# magnet-node.net
KiCad netlist of a schematic drawn in EAGLE
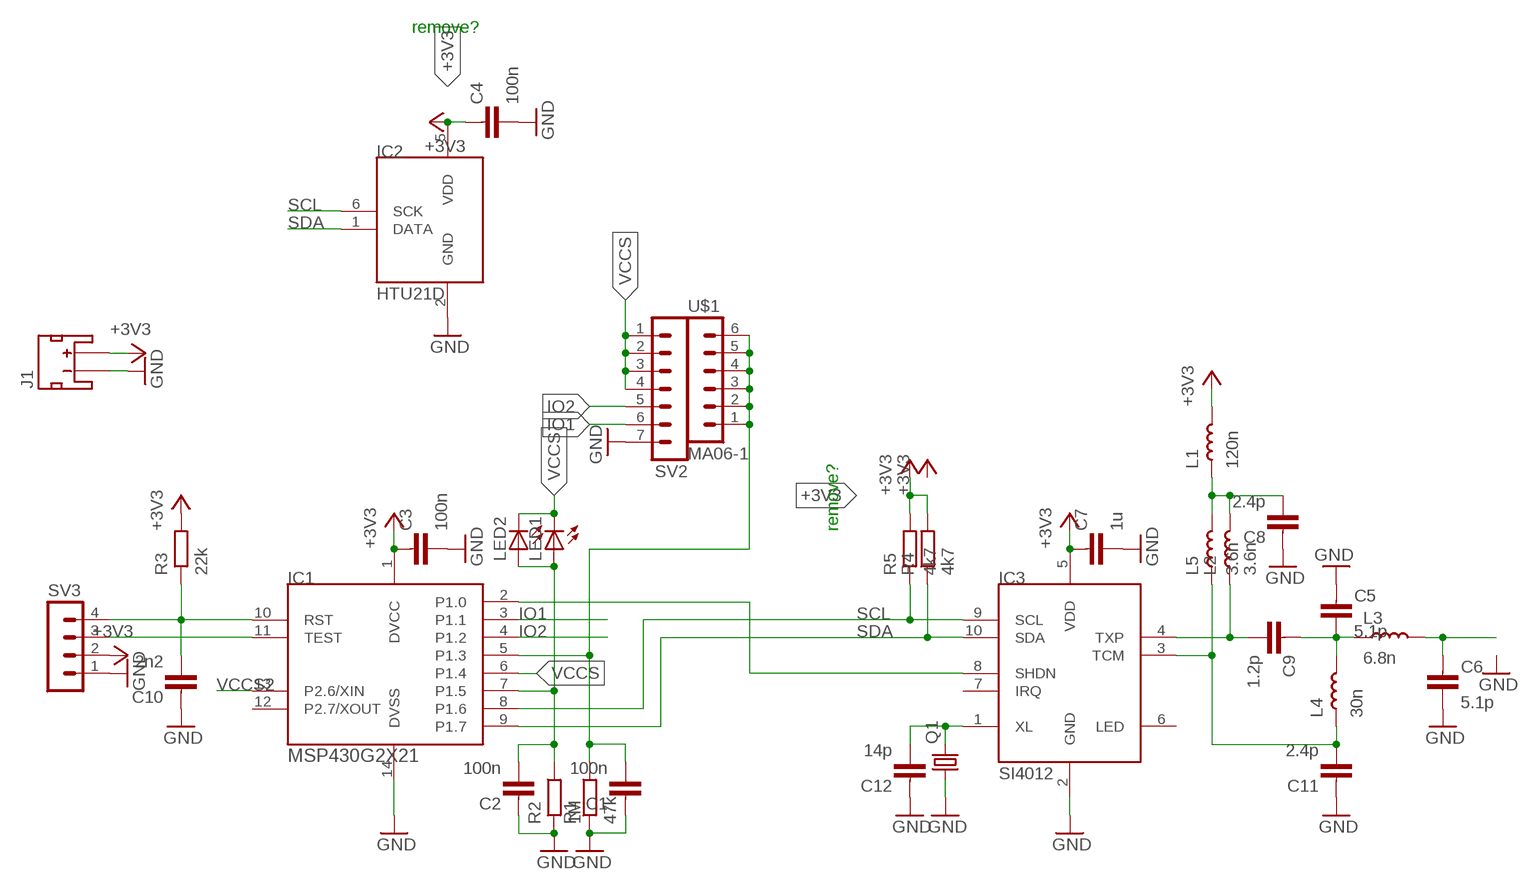
[diagram p0: schematic, sheet 1]

(export (version "E")
  (design (tool "Eeschema 10.0.6"))
  (components
    (comp (ref "C1")
      (value "100n")
      (footprint "eagle-import:C0603-N")
      (libsource (lib "eagle-import") (part "CAPACITOR0603-N"))
    )
    (comp (ref "C2")
      (value "100n")
      (footprint "eagle-import:C0603-N")
      (libsource (lib "eagle-import") (part "CAPACITOR0603-N"))
    )
    (comp (ref "C3")
      (value "100n")
      (footprint "eagle-import:C0603-N")
      (libsource (lib "eagle-import") (part "CAPACITOR0603-N"))
    )
    (comp (ref "C4")
      (value "100n")
      (footprint "eagle-import:C0603-N")
      (libsource (lib "eagle-import") (part "CAPACITOR0603-N"))
    )
    (comp (ref "C5")
      (value "5.1p")
      (footprint "eagle-import:C0603-N")
      (libsource (lib "eagle-import") (part "CAPACITOR0603-N"))
    )
    (comp (ref "C6")
      (value "5.1p")
      (footprint "eagle-import:C0603-N")
      (libsource (lib "eagle-import") (part "CAPACITOR0603-N"))
    )
    (comp (ref "C7")
      (value "1u")
      (footprint "eagle-import:C0603-N")
      (libsource (lib "eagle-import") (part "CAPACITOR0603-N"))
    )
    (comp (ref "C8")
      (value "2.4p")
      (footprint "eagle-import:C0603-N")
      (libsource (lib "eagle-import") (part "CAPACITOR0603-N"))
    )
    (comp (ref "C9")
      (value "1.2p")
      (footprint "eagle-import:C0603-N")
      (libsource (lib "eagle-import") (part "CAPACITOR0603-N"))
    )
    (comp (ref "C10")
      (value "2n2")
      (footprint "eagle-import:C0603-N")
      (libsource (lib "eagle-import") (part "CAPACITOR0603-N"))
    )
    (comp (ref "C11")
      (value "2.4p")
      (footprint "eagle-import:C0603-N")
      (libsource (lib "eagle-import") (part "CAPACITOR0603-N"))
    )
    (comp (ref "C12")
      (value "14p")
      (footprint "eagle-import:C0603-N")
      (libsource (lib "eagle-import") (part "CAPACITOR0603-N"))
    )
    (comp (ref "IC1")
      (value "MSP430G2X21")
      (footprint "eagle-import:TSSOP14")
      (libsource (lib "eagle-import") (part "MSP430G2X21"))
    )
    (comp (ref "IC2")
      (value "HTU21D")
      (footprint "eagle-import:DFN6-L")
      (libsource (lib "eagle-import") (part "HTU21D"))
    )
    (comp (ref "IC3")
      (value "SI4012")
      (footprint "eagle-import:MSOP10")
      (libsource (lib "eagle-import") (part "SI4012"))
    )
    (comp (ref "J1")
      (value "JST_2MM_MALE_TH")
      (footprint "eagle-import:JST-2-TH")
      (libsource (lib "eagle-import") (part "JST_2MM_MALE_TH"))
    )
    (comp (ref "L1")
      (value "120n")
      (footprint "eagle-import:L0603-N")
      (libsource (lib "eagle-import") (part "INDUCTOR0603-N"))
    )
    (comp (ref "L2")
      (value "3.6n")
      (footprint "eagle-import:L0402-N")
      (libsource (lib "eagle-import") (part "INDUCTOR0402-N"))
    )
    (comp (ref "L3")
      (value "6.8n")
      (footprint "eagle-import:L0402-N")
      (libsource (lib "eagle-import") (part "INDUCTOR0402-N"))
    )
    (comp (ref "L4")
      (value "30n")
      (footprint "eagle-import:L0402-N")
      (libsource (lib "eagle-import") (part "INDUCTOR0402-N"))
    )
    (comp (ref "L5")
      (value "3.6n")
      (footprint "eagle-import:L0402-N")
      (libsource (lib "eagle-import") (part "INDUCTOR0402-N"))
    )
    (comp (ref "LED1")
      (value "LEDSMT1206")
      (footprint "eagle-import:1206")
      (libsource (lib "eagle-import") (part "LEDSMT1206"))
    )
    (comp (ref "LED2")
      (value "LEDSMT1206")
      (footprint "eagle-import:1206")
      (libsource (lib "eagle-import") (part "LEDSMT1206"))
    )
    (comp (ref "Q1")
      (value "CRYSTALHC49S")
      (footprint "eagle-import:HC49_S")
      (libsource (lib "eagle-import") (part "CRYSTALHC49S"))
    )
    (comp (ref "R1")
      (value "47k")
      (footprint "eagle-import:R0603-N")
      (libsource (lib "eagle-import") (part "RESISTOR0603-N"))
    )
    (comp (ref "R2")
      (value "1M")
      (footprint "eagle-import:R0603-N")
      (libsource (lib "eagle-import") (part "RESISTOR0603-N"))
    )
    (comp (ref "R3")
      (value "22k")
      (footprint "eagle-import:R0603-N")
      (libsource (lib "eagle-import") (part "RESISTOR0603-N"))
    )
    (comp (ref "R4")
      (value "4k7")
      (footprint "eagle-import:R0603-N")
      (libsource (lib "eagle-import") (part "RESISTOR0603-N"))
    )
    (comp (ref "R5")
      (value "4k7")
      (footprint "eagle-import:R0603-N")
      (libsource (lib "eagle-import") (part "RESISTOR0603-N"))
    )
    (comp (ref "SV2")
      (value "MA07-1S")
      (footprint "eagle-import:MA07-1-SMD")
      (libsource (lib "eagle-import") (part "MA07-1S"))
    )
    (comp (ref "SV3")
      (value "MA04-1E")
      (footprint "eagle-import:EDGE_4")
      (libsource (lib "eagle-import") (part "MA04-1E"))
    )
    (comp (ref "U$1")
      (value "MA06-1")
      (footprint "eagle-import:MA06-1-SMD")
      (libsource (lib "eagle-import") (part "MA06-1"))
    )
  )
  (nets
    (net (code "1") (name "+3V3") (class "Default")
      (node (ref "C3") (pin "1") (pinfunction "1_1") (pintype "passive"))
      (node (ref "C4") (pin "1") (pinfunction "1_1") (pintype "passive"))
      (node (ref "C7") (pin "1") (pinfunction "1_1") (pintype "passive"))
      (node (ref "IC1") (pin "1") (pinfunction "DVCC_1") (pintype "power_in"))
      (node (ref "IC2") (pin "5") (pinfunction "VDD_5") (pintype "power_in"))
      (node (ref "IC3") (pin "5") (pinfunction "VDD_5") (pintype "power_in"))
      (node (ref "J1") (pin "1") (pinfunction "+_1") (pintype "bidirectional"))
      (node (ref "L1") (pin "2") (pinfunction "P$2_2") (pintype "passive"))
      (node (ref "R3") (pin "2") (pinfunction "P$2_2") (pintype "passive"))
      (node (ref "R4") (pin "2") (pinfunction "P$2_2") (pintype "passive"))
      (node (ref "R5") (pin "2") (pinfunction "P$2_2") (pintype "passive"))
      (node (ref "SV3") (pin "2") (pinfunction "2_2") (pintype "passive"))
    )
    (net (code "2") (name "/SCL") (class "Default")
      (node (ref "IC1") (pin "8") (pinfunction "P1.6_8") (pintype "bidirectional"))
      (node (ref "IC2") (pin "6") (pinfunction "SCK_6") (pintype "input"))
      (node (ref "IC3") (pin "9") (pinfunction "SCL_9") (pintype "input"))
      (node (ref "R5") (pin "1") (pinfunction "P$1_1") (pintype "passive"))
    )
    (net (code "3") (name "/SDA") (class "Default")
      (node (ref "IC1") (pin "9") (pinfunction "P1.7_9") (pintype "bidirectional"))
      (node (ref "IC2") (pin "1") (pinfunction "DATA_1") (pintype "bidirectional"))
      (node (ref "IC3") (pin "10") (pinfunction "SDA_10") (pintype "bidirectional"))
      (node (ref "R4") (pin "1") (pinfunction "P$1_1") (pintype "passive"))
    )
    (net (code "4") (name "/VCCS2") (class "Default")
      (node (ref "IC1") (pin "13") (pinfunction "P2.6/XIN_13") (pintype "bidirectional"))
    )
    (net (code "5") (name "GND") (class "Default")
      (node (ref "C1") (pin "1") (pinfunction "1_1") (pintype "passive"))
      (node (ref "C10") (pin "1") (pinfunction "1_1") (pintype "passive"))
      (node (ref "C11") (pin "1") (pinfunction "1_1") (pintype "passive"))
      (node (ref "C12") (pin "1") (pinfunction "1_1") (pintype "passive"))
      (node (ref "C2") (pin "1") (pinfunction "1_1") (pintype "passive"))
      (node (ref "C3") (pin "2") (pinfunction "2_2") (pintype "passive"))
      (node (ref "C4") (pin "2") (pinfunction "2_2") (pintype "passive"))
      (node (ref "C5") (pin "1") (pinfunction "1_1") (pintype "passive"))
      (node (ref "C6") (pin "2") (pinfunction "2_2") (pintype "passive"))
      (node (ref "C7") (pin "2") (pinfunction "2_2") (pintype "passive"))
      (node (ref "C8") (pin "1") (pinfunction "1_1") (pintype "passive"))
      (node (ref "IC1") (pin "14") (pinfunction "DVSS_14") (pintype "power_in"))
      (node (ref "IC2") (pin "2") (pinfunction "GND_2") (pintype "power_in"))
      (node (ref "IC3") (pin "2") (pinfunction "GND_2") (pintype "power_in"))
      (node (ref "J1") (pin "2") (pinfunction "-_2") (pintype "bidirectional"))
      (node (ref "Q1") (pin "1") (pinfunction "1_1") (pintype "passive"))
      (node (ref "R1") (pin "1") (pinfunction "P$1_1") (pintype "passive"))
      (node (ref "R2") (pin "1") (pinfunction "P$1_1") (pintype "passive"))
      (node (ref "SV2") (pin "7") (pinfunction "7_7") (pintype "passive"))
      (node (ref "SV3") (pin "1") (pinfunction "1_1") (pintype "passive"))
    )
    (net (code "6") (name "IO1") (class "Default")
      (node (ref "IC1") (pin "3") (pinfunction "P1.1_3") (pintype "bidirectional"))
      (node (ref "SV2") (pin "6") (pinfunction "6_6") (pintype "passive"))
    )
    (net (code "7") (name "IO2") (class "Default")
      (node (ref "IC1") (pin "4") (pinfunction "P1.2_4") (pintype "bidirectional"))
      (node (ref "SV2") (pin "5") (pinfunction "5_5") (pintype "passive"))
    )
    (net (code "8") (name "Net-(IC1-P1.0)") (class "Default")
      (node (ref "IC1") (pin "2") (pinfunction "P1.0_2") (pintype "bidirectional"))
      (node (ref "IC3") (pin "8") (pinfunction "SHDN_8") (pintype "input"))
    )
    (net (code "9") (name "Net-(IC1-P1.3)") (class "Default")
      (node (ref "C1") (pin "2") (pinfunction "2_2") (pintype "passive"))
      (node (ref "IC1") (pin "5") (pinfunction "P1.3_5") (pintype "bidirectional"))
      (node (ref "R1") (pin "2") (pinfunction "P$2_2") (pintype "passive"))
      (node (ref "U$1") (pin "1") (pinfunction "1_1") (pintype "passive"))
      (node (ref "U$1") (pin "2") (pinfunction "2_2") (pintype "passive"))
      (node (ref "U$1") (pin "3") (pinfunction "3_3") (pintype "passive"))
      (node (ref "U$1") (pin "4") (pinfunction "4_4") (pintype "passive"))
      (node (ref "U$1") (pin "5") (pinfunction "5_5") (pintype "passive"))
      (node (ref "U$1") (pin "6") (pinfunction "6_6") (pintype "passive"))
    )
    (net (code "10") (name "Net-(IC1-P1.5)") (class "Default")
      (node (ref "C2") (pin "2") (pinfunction "2_2") (pintype "passive"))
      (node (ref "IC1") (pin "7") (pinfunction "P1.5_7") (pintype "bidirectional"))
      (node (ref "LED1") (pin "A") (pinfunction "A_A") (pintype "passive"))
      (node (ref "LED2") (pin "A") (pinfunction "A_A") (pintype "passive"))
      (node (ref "R2") (pin "2") (pinfunction "P$2_2") (pintype "passive"))
    )
    (net (code "11") (name "Net-(IC1-RST)") (class "Default")
      (node (ref "C10") (pin "2") (pinfunction "2_2") (pintype "passive"))
      (node (ref "IC1") (pin "10") (pinfunction "RST_10") (pintype "bidirectional"))
      (node (ref "R3") (pin "1") (pinfunction "P$1_1") (pintype "passive"))
      (node (ref "SV3") (pin "4") (pinfunction "4_4") (pintype "passive"))
    )
    (net (code "12") (name "Net-(IC1-TEST)") (class "Default")
      (node (ref "IC1") (pin "11") (pinfunction "TEST_11") (pintype "bidirectional"))
      (node (ref "SV3") (pin "3") (pinfunction "3_3") (pintype "passive"))
    )
    (net (code "13") (name "Net-(IC3-TCM)") (class "Default")
      (node (ref "C11") (pin "2") (pinfunction "2_2") (pintype "passive"))
      (node (ref "IC3") (pin "3") (pinfunction "TCM_3") (pintype "output"))
      (node (ref "L4") (pin "1") (pinfunction "P$1_1") (pintype "passive"))
      (node (ref "L5") (pin "1") (pinfunction "P$1_1") (pintype "passive"))
    )
    (net (code "14") (name "Net-(IC3-TXP)") (class "Default")
      (node (ref "C9") (pin "2") (pinfunction "2_2") (pintype "passive"))
      (node (ref "IC3") (pin "4") (pinfunction "TXP_4") (pintype "output"))
      (node (ref "L2") (pin "1") (pinfunction "P$1_1") (pintype "passive"))
    )
    (net (code "15") (name "Net-(IC3-XL)") (class "Default")
      (node (ref "C12") (pin "2") (pinfunction "2_2") (pintype "passive"))
      (node (ref "IC3") (pin "1") (pinfunction "XL_1") (pintype "bidirectional"))
      (node (ref "Q1") (pin "2") (pinfunction "2_2") (pintype "passive"))
    )
    (net (code "16") (name "Net-(L1-P$1)") (class "Default")
      (node (ref "C8") (pin "2") (pinfunction "2_2") (pintype "passive"))
      (node (ref "L1") (pin "1") (pinfunction "P$1_1") (pintype "passive"))
      (node (ref "L2") (pin "2") (pinfunction "P$2_2") (pintype "passive"))
      (node (ref "L5") (pin "2") (pinfunction "P$2_2") (pintype "passive"))
    )
    (net (code "17") (name "Net-(L3-P$1)") (class "Default")
      (node (ref "C5") (pin "2") (pinfunction "2_2") (pintype "passive"))
      (node (ref "C9") (pin "1") (pinfunction "1_1") (pintype "passive"))
      (node (ref "L3") (pin "1") (pinfunction "P$1_1") (pintype "passive"))
      (node (ref "L4") (pin "2") (pinfunction "P$2_2") (pintype "passive"))
    )
    (net (code "18") (name "Net-(L3-P$2)") (class "Default")
      (node (ref "C6") (pin "1") (pinfunction "1_1") (pintype "passive"))
      (node (ref "L3") (pin "2") (pinfunction "P$2_2") (pintype "passive"))
    )
    (net (code "19") (name "VCCS") (class "Default")
      (node (ref "IC1") (pin "6") (pinfunction "P1.4_6") (pintype "bidirectional"))
      (node (ref "LED1") (pin "C") (pinfunction "C_C") (pintype "passive"))
      (node (ref "LED2") (pin "C") (pinfunction "C_C") (pintype "passive"))
      (node (ref "SV2") (pin "1") (pinfunction "1_1") (pintype "passive"))
      (node (ref "SV2") (pin "2") (pinfunction "2_2") (pintype "passive"))
      (node (ref "SV2") (pin "3") (pinfunction "3_3") (pintype "passive"))
      (node (ref "SV2") (pin "4") (pinfunction "4_4") (pintype "passive"))
    )
    (net (code "20") (name "unconnected-(IC1-P2.7{slash}XOUT-Pad12)") (class "Default")
      (node (ref "IC1") (pin "12") (pinfunction "P2.7/XOUT_12") (pintype "bidirectional"))
    )
    (net (code "21") (name "unconnected-(IC3-IRQ-Pad7)") (class "Default")
      (node (ref "IC3") (pin "7") (pinfunction "IRQ_7") (pintype "output"))
    )
    (net (code "22") (name "unconnected-(IC3-LED-Pad6)") (class "Default")
      (node (ref "IC3") (pin "6") (pinfunction "LED_6") (pintype "output"))
    )
  )
)
